# EMG_Sensors_Temp.net
KiCad netlist of a schematic drawn in Altium Designer
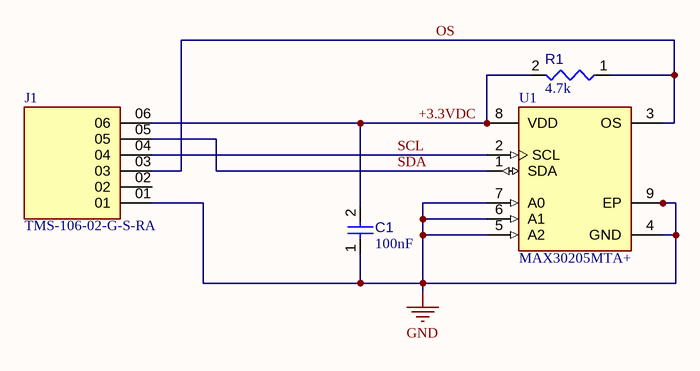
[diagram p0: EMG_Sensors_Temp.SchDoc]

(export (version "E")
  (design (tool "Eeschema 10.0.6"))
  (components
    (comp (ref "C1")
      (value "100nF")
      (footprint "CAPC1005X56X25LL10T15")
      (description "Chip Capacitor, 0.1 uF, +/- 5%, 16 V, 0402 (1005 Metric)")
      (fields (field (name "TOLERANCE") "5%") (field (name "Comment") "Capacitor 0.1 uF +/- 5% 16 V 0402"))
      (libsource (lib "Education") (part "CAP-NP-2"))
    )
    (comp (ref "J1")
      (value "TMS-106-02-G-S-RA")
      (footprint "SAMTEC_TMS-106-02-G-S-RA")
      (libsource (lib "TMS-106-02-G-S-RA") (part "TMS-106-02-G-S-RA"))
    )
    (comp (ref "R1")
      (value "4.7k")
      (footprint "RESC1005X40X25ML05T05")
      (description "Chip Resistor, 4.7 KOhm, +/- 1%, 63 mW, -55 to 155 degC, 0402 (1005 Metric)")
      (fields (field (name "TOLERANCE") "1%") (field (name "POWER") "63mW"))
      (libsource (lib "Education") (part "RES-2"))
    )
    (comp (ref "U1")
      (value "MAX30205MTA+")
      (footprint "FP-T833-2-MFG")
      (description "SENSOR DIGITAL 0C-50C 8TDFN")
      (fields
        (field (name "MANUFACTURER") "Maxim Integrated")
        (field (name "OCTOPART") "https://octopart.com/max30205mta%2B-maxim+integrated-66461181")
      )
      (libsource (lib "Altium Content Vault") (part "9a6461b16ab1fc7bdb122d4777b4449"))
    )
  )
  (nets
    (net (code "1") (name "/+3.3VDC") (class "Default")
      (node (ref "C1") (pin "2") (pinfunction "2_2") (pintype "passive"))
      (node (ref "J1") (pin "06") (pinfunction "06_06") (pintype "passive"))
      (node (ref "R1") (pin "2") (pinfunction "2_2") (pintype "passive"))
      (node (ref "U1") (pin "8") (pinfunction "VDD_8") (pintype "power_in"))
    )
    (net (code "2") (name "/OS") (class "Default")
      (node (ref "J1") (pin "03") (pinfunction "03_03") (pintype "passive"))
      (node (ref "R1") (pin "1") (pinfunction "1_1") (pintype "passive"))
      (node (ref "U1") (pin "3") (pinfunction "OS_3") (pintype "open_collector"))
    )
    (net (code "3") (name "/SCL") (class "Default")
      (node (ref "J1") (pin "04") (pinfunction "04_04") (pintype "passive"))
      (node (ref "U1") (pin "2") (pinfunction "SCL_2") (pintype "input"))
    )
    (net (code "4") (name "/SDA") (class "Default")
      (node (ref "J1") (pin "05") (pinfunction "05_05") (pintype "passive"))
      (node (ref "U1") (pin "1") (pinfunction "SDA_1") (pintype "bidirectional"))
    )
    (net (code "5") (name "GND") (class "Default")
      (node (ref "C1") (pin "1") (pinfunction "1_1") (pintype "passive"))
      (node (ref "J1") (pin "01") (pinfunction "01_01") (pintype "passive"))
      (node (ref "U1") (pin "4") (pinfunction "GND_4") (pintype "power_in"))
      (node (ref "U1") (pin "5") (pinfunction "A2_5") (pintype "input"))
      (node (ref "U1") (pin "6") (pinfunction "A1_6") (pintype "input"))
      (node (ref "U1") (pin "7") (pinfunction "A0_7") (pintype "input"))
      (node (ref "U1") (pin "9") (pinfunction "EP_9") (pintype "power_in"))
    )
    (net (code "6") (name "unconnected-(J1-Pad02)") (class "Default")
      (node (ref "J1") (pin "02") (pinfunction "02_02") (pintype "passive"))
    )
  )
)
